# xlrconn.net
KiCad netlist of a schematic drawn in Altium Designer
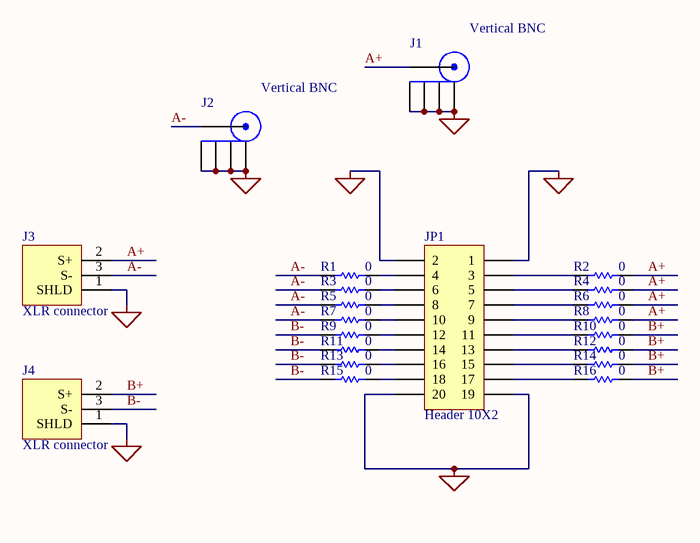
[diagram p0: xlrconn.SCHDOC]

(export (version "E")
  (design (tool "Eeschema 10.0.6"))
  (components
    (comp (ref "J1")
      (value "Vertical BNC")
      (footprint "Vertical BNC 227699-1")
      (description "Vertical BNC with correct grounding pin behavior")
      (libsource (lib "My devices") (part "VERTBNC"))
    )
    (comp (ref "J2")
      (value "Vertical BNC")
      (footprint "Vertical BNC 227699-1")
      (description "Vertical BNC with correct grounding pin behavior")
      (libsource (lib "My devices") (part "VERTBNC"))
    )
    (comp (ref "J3")
      (value "XLR connector")
      (footprint "NC3FAH-0")
      (description "XLR balanced connector, standard")
      (libsource (lib "My devices") (part "XLR"))
    )
    (comp (ref "J4")
      (value "XLR connector")
      (footprint "NC3FAH-0")
      (description "XLR balanced connector, standard")
      (libsource (lib "My devices") (part "XLR"))
    )
    (comp (ref "JP1")
      (value "Header 10X2")
      (footprint "HDR2X10")
      (description "Header, 10-Pin, Dual row")
      (fields (field (name "MANUFACTURER") "Generic Components") (field (name "PUBLISHER") "Altium Limited"))
      (libsource (lib "Miscellaneous Connectors") (part "Header 10X2"))
    )
    (comp (ref "R1")
      (value "0")
      (footprint "CR1005-0402")
      (description "Resistor")
      (fields (field (name "PUBLISHER") "Altium Limited"))
      (libsource (lib "Miscellaneous Devices") (part "Res1"))
    )
    (comp (ref "R2")
      (value "0")
      (footprint "CR1005-0402")
      (description "Resistor")
      (fields (field (name "PUBLISHER") "Altium Limited"))
      (libsource (lib "Miscellaneous Devices") (part "Res1"))
    )
    (comp (ref "R3")
      (value "0")
      (footprint "CR1005-0402")
      (description "Resistor")
      (fields (field (name "PUBLISHER") "Altium Limited"))
      (libsource (lib "Miscellaneous Devices") (part "Res1"))
    )
    (comp (ref "R4")
      (value "0")
      (footprint "CR1005-0402")
      (description "Resistor")
      (fields (field (name "PUBLISHER") "Altium Limited"))
      (libsource (lib "Miscellaneous Devices") (part "Res1"))
    )
    (comp (ref "R5")
      (value "0")
      (footprint "CR1005-0402")
      (description "Resistor")
      (fields (field (name "PUBLISHER") "Altium Limited"))
      (libsource (lib "Miscellaneous Devices") (part "Res1"))
    )
    (comp (ref "R6")
      (value "0")
      (footprint "CR1005-0402")
      (description "Resistor")
      (fields (field (name "PUBLISHER") "Altium Limited"))
      (libsource (lib "Miscellaneous Devices") (part "Res1"))
    )
    (comp (ref "R7")
      (value "0")
      (footprint "CR1005-0402")
      (description "Resistor")
      (fields (field (name "PUBLISHER") "Altium Limited"))
      (libsource (lib "Miscellaneous Devices") (part "Res1"))
    )
    (comp (ref "R8")
      (value "0")
      (footprint "CR1005-0402")
      (description "Resistor")
      (fields (field (name "PUBLISHER") "Altium Limited"))
      (libsource (lib "Miscellaneous Devices") (part "Res1"))
    )
    (comp (ref "R9")
      (value "0")
      (footprint "CR1005-0402")
      (description "Resistor")
      (fields (field (name "PUBLISHER") "Altium Limited"))
      (libsource (lib "Miscellaneous Devices") (part "Res1"))
    )
    (comp (ref "R10")
      (value "0")
      (footprint "CR1005-0402")
      (description "Resistor")
      (fields (field (name "PUBLISHER") "Altium Limited"))
      (libsource (lib "Miscellaneous Devices") (part "Res1"))
    )
    (comp (ref "R11")
      (value "0")
      (footprint "CR1005-0402")
      (description "Resistor")
      (fields (field (name "PUBLISHER") "Altium Limited"))
      (libsource (lib "Miscellaneous Devices") (part "Res1"))
    )
    (comp (ref "R12")
      (value "0")
      (footprint "CR1005-0402")
      (description "Resistor")
      (fields (field (name "PUBLISHER") "Altium Limited"))
      (libsource (lib "Miscellaneous Devices") (part "Res1"))
    )
    (comp (ref "R13")
      (value "0")
      (footprint "CR1005-0402")
      (description "Resistor")
      (fields (field (name "PUBLISHER") "Altium Limited"))
      (libsource (lib "Miscellaneous Devices") (part "Res1"))
    )
    (comp (ref "R14")
      (value "0")
      (footprint "CR1005-0402")
      (description "Resistor")
      (fields (field (name "PUBLISHER") "Altium Limited"))
      (libsource (lib "Miscellaneous Devices") (part "Res1"))
    )
    (comp (ref "R15")
      (value "0")
      (footprint "CR1005-0402")
      (description "Resistor")
      (fields (field (name "PUBLISHER") "Altium Limited"))
      (libsource (lib "Miscellaneous Devices") (part "Res1"))
    )
    (comp (ref "R16")
      (value "0")
      (footprint "CR1005-0402")
      (description "Resistor")
      (fields (field (name "PUBLISHER") "Altium Limited"))
      (libsource (lib "Miscellaneous Devices") (part "Res1"))
    )
  )
  (nets
    (net (code "1") (name "/A+") (class "Default")
      (node (ref "J1") (pin "1") (pinfunction "PIN_1") (pintype "passive"))
      (node (ref "J3") (pin "2") (pinfunction "S+_2") (pintype "passive"))
      (node (ref "R2") (pin "2") (pinfunction "2_2") (pintype "passive"))
      (node (ref "R4") (pin "2") (pinfunction "2_2") (pintype "passive"))
      (node (ref "R6") (pin "2") (pinfunction "2_2") (pintype "passive"))
      (node (ref "R8") (pin "2") (pinfunction "2_2") (pintype "passive"))
    )
    (net (code "2") (name "/A-") (class "Default")
      (node (ref "J2") (pin "1") (pinfunction "PIN_1") (pintype "passive"))
      (node (ref "J3") (pin "3") (pinfunction "S-_3") (pintype "passive"))
      (node (ref "R1") (pin "1") (pinfunction "1_1") (pintype "passive"))
      (node (ref "R3") (pin "1") (pinfunction "1_1") (pintype "passive"))
      (node (ref "R5") (pin "1") (pinfunction "1_1") (pintype "passive"))
      (node (ref "R7") (pin "1") (pinfunction "1_1") (pintype "passive"))
    )
    (net (code "3") (name "/B+") (class "Default")
      (node (ref "J4") (pin "2") (pinfunction "S+_2") (pintype "passive"))
      (node (ref "R10") (pin "2") (pinfunction "2_2") (pintype "passive"))
      (node (ref "R12") (pin "2") (pinfunction "2_2") (pintype "passive"))
      (node (ref "R14") (pin "2") (pinfunction "2_2") (pintype "passive"))
      (node (ref "R16") (pin "2") (pinfunction "2_2") (pintype "passive"))
    )
    (net (code "4") (name "/B-") (class "Default")
      (node (ref "J4") (pin "3") (pinfunction "S-_3") (pintype "passive"))
      (node (ref "R11") (pin "1") (pinfunction "1_1") (pintype "passive"))
      (node (ref "R13") (pin "1") (pinfunction "1_1") (pintype "passive"))
      (node (ref "R15") (pin "1") (pinfunction "1_1") (pintype "passive"))
      (node (ref "R9") (pin "1") (pinfunction "1_1") (pintype "passive"))
    )
    (net (code "5") (name "GND") (class "Default")
      (node (ref "J1") (pin "2") (pinfunction "SHLD_2") (pintype "passive"))
      (node (ref "J1") (pin "3") (pinfunction "SHLD_3") (pintype "passive"))
      (node (ref "J1") (pin "4") (pinfunction "SHLD_4") (pintype "passive"))
      (node (ref "J1") (pin "5") (pinfunction "SHLD_5") (pintype "passive"))
      (node (ref "J2") (pin "2") (pinfunction "SHLD_2") (pintype "passive"))
      (node (ref "J2") (pin "3") (pinfunction "SHLD_3") (pintype "passive"))
      (node (ref "J2") (pin "4") (pinfunction "SHLD_4") (pintype "passive"))
      (node (ref "J2") (pin "5") (pinfunction "SHLD_5") (pintype "passive"))
      (node (ref "J3") (pin "1") (pinfunction "SHLD_1") (pintype "passive"))
      (node (ref "J4") (pin "1") (pinfunction "SHLD_1") (pintype "passive"))
      (node (ref "JP1") (pin "1") (pinfunction "1_1") (pintype "passive"))
      (node (ref "JP1") (pin "19") (pinfunction "19_19") (pintype "passive"))
      (node (ref "JP1") (pin "2") (pinfunction "2_2") (pintype "passive"))
      (node (ref "JP1") (pin "20") (pinfunction "20_20") (pintype "passive"))
    )
    (net (code "6") (name "Net-(JP1-Pad3)") (class "Default")
      (node (ref "JP1") (pin "3") (pinfunction "3_3") (pintype "passive"))
      (node (ref "R2") (pin "1") (pinfunction "1_1") (pintype "passive"))
    )
    (net (code "7") (name "Net-(JP1-Pad4)") (class "Default")
      (node (ref "JP1") (pin "4") (pinfunction "4_4") (pintype "passive"))
      (node (ref "R1") (pin "2") (pinfunction "2_2") (pintype "passive"))
    )
    (net (code "8") (name "Net-(JP1-Pad5)") (class "Default")
      (node (ref "JP1") (pin "5") (pinfunction "5_5") (pintype "passive"))
      (node (ref "R4") (pin "1") (pinfunction "1_1") (pintype "passive"))
    )
    (net (code "9") (name "Net-(JP1-Pad6)") (class "Default")
      (node (ref "JP1") (pin "6") (pinfunction "6_6") (pintype "passive"))
      (node (ref "R3") (pin "2") (pinfunction "2_2") (pintype "passive"))
    )
    (net (code "10") (name "Net-(JP1-Pad7)") (class "Default")
      (node (ref "JP1") (pin "7") (pinfunction "7_7") (pintype "passive"))
      (node (ref "R6") (pin "1") (pinfunction "1_1") (pintype "passive"))
    )
    (net (code "11") (name "Net-(JP1-Pad8)") (class "Default")
      (node (ref "JP1") (pin "8") (pinfunction "8_8") (pintype "passive"))
      (node (ref "R5") (pin "2") (pinfunction "2_2") (pintype "passive"))
    )
    (net (code "12") (name "Net-(JP1-Pad9)") (class "Default")
      (node (ref "JP1") (pin "9") (pinfunction "9_9") (pintype "passive"))
      (node (ref "R8") (pin "1") (pinfunction "1_1") (pintype "passive"))
    )
    (net (code "13") (name "Net-(JP1-Pad10)") (class "Default")
      (node (ref "JP1") (pin "10") (pinfunction "10_10") (pintype "passive"))
      (node (ref "R7") (pin "2") (pinfunction "2_2") (pintype "passive"))
    )
    (net (code "14") (name "Net-(JP1-Pad11)") (class "Default")
      (node (ref "JP1") (pin "11") (pinfunction "11_11") (pintype "passive"))
      (node (ref "R10") (pin "1") (pinfunction "1_1") (pintype "passive"))
    )
    (net (code "15") (name "Net-(JP1-Pad12)") (class "Default")
      (node (ref "JP1") (pin "12") (pinfunction "12_12") (pintype "passive"))
      (node (ref "R9") (pin "2") (pinfunction "2_2") (pintype "passive"))
    )
    (net (code "16") (name "Net-(JP1-Pad13)") (class "Default")
      (node (ref "JP1") (pin "13") (pinfunction "13_13") (pintype "passive"))
      (node (ref "R12") (pin "1") (pinfunction "1_1") (pintype "passive"))
    )
    (net (code "17") (name "Net-(JP1-Pad14)") (class "Default")
      (node (ref "JP1") (pin "14") (pinfunction "14_14") (pintype "passive"))
      (node (ref "R11") (pin "2") (pinfunction "2_2") (pintype "passive"))
    )
    (net (code "18") (name "Net-(JP1-Pad15)") (class "Default")
      (node (ref "JP1") (pin "15") (pinfunction "15_15") (pintype "passive"))
      (node (ref "R14") (pin "1") (pinfunction "1_1") (pintype "passive"))
    )
    (net (code "19") (name "Net-(JP1-Pad16)") (class "Default")
      (node (ref "JP1") (pin "16") (pinfunction "16_16") (pintype "passive"))
      (node (ref "R13") (pin "2") (pinfunction "2_2") (pintype "passive"))
    )
    (net (code "20") (name "Net-(JP1-Pad17)") (class "Default")
      (node (ref "JP1") (pin "17") (pinfunction "17_17") (pintype "passive"))
      (node (ref "R16") (pin "1") (pinfunction "1_1") (pintype "passive"))
    )
    (net (code "21") (name "Net-(JP1-Pad18)") (class "Default")
      (node (ref "JP1") (pin "18") (pinfunction "18_18") (pintype "passive"))
      (node (ref "R15") (pin "2") (pinfunction "2_2") (pintype "passive"))
    )
  )
)
